# TopSheet.net
KiCad netlist of a schematic drawn in Altium Designer
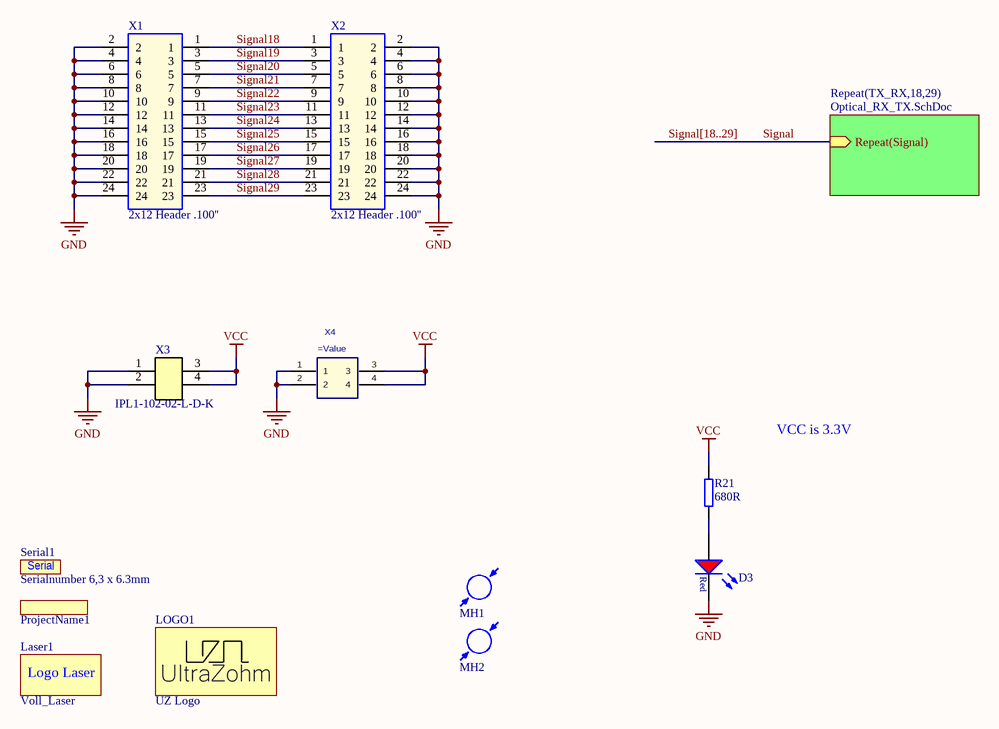
[diagram p0: TopSheet.SchDoc]

(export (version "E")
  (design (tool "Eeschema 10.0.6"))
  (components
    (comp (ref "D3")
      (value "150060RS75000")
      (footprint "WL-SMCW_0603")
      (description "WL-SMCW SMD Mono-color Chip LED Waterclear, size 0603, Red, 2 V, 140°")
      (fields
        (field (name "MF") "Wuerth Elektronik")
        (field (name "LCSC PART NUMBER") "C2286")
        (field (name "CREATED") "2018_09_06_AGeiger")
      )
      (libsource (lib "UZOhm_Optical") (part "LED_Red_0603"))
    )
    (comp (ref "Laser1")
      (value "Voll_Laser")
      (footprint "Voll_Laser")
      (description "Logo Laser Warning Sign")
      (libsource (lib "UZOhm_Optical") (part "Voll_Laser"))
    )
    (comp (ref "LOGO1")
      (value "UZ Logo")
      (footprint "UZ_Logo_small")
      (description "UltraZohm Logo on PCB")
      (fields (field (name "CREATED") "Jan2021_Liegmann"))
      (libsource (lib "PCB_Logo") (part "UZ Logo"))
    )
    (comp (ref "MH1")
      (value "MH_2.8")
      (footprint "MH_2.8")
      (description "Non plated through hole")
      (libsource (lib "UZOhm_Optical") (part "Mounting Hole"))
    )
    (comp (ref "MH2")
      (value "MH_2.8")
      (footprint "MH_2.8")
      (description "Non plated through hole")
      (libsource (lib "UZOhm_Optical") (part "Mounting Hole"))
    )
    (comp (ref "ProjectName1")
      (value "Project Name, Rev")
      (footprint "ID_ProjectRev")
      (description "Project Name and Revision Number")
      (fields (field (name "CREATED") "2018_11_23_AGeiger"))
      (libsource (lib "UZOhm_Optical") (part "ID_ProjectRev"))
    )
    (comp (ref "R21")
      (value "680R")
      (footprint "R_0603_N")
      (description "SMD Resistor 0603")
      (fields
        (field (name "TOLERANCE") "1%")
        (field (name "VOLTAGE") "75V")
        (field (name "CREATED") "2018_09_06_AGeiger")
      )
      (libsource (lib "UZOhm_Optical") (part "R_0603"))
    )
    (comp (ref "Serial1")
      (value "Serialnumber 6,3 x 6.3mm")
      (footprint "Serial_6.3x6.3mm")
      (fields (field (name "CREATED") "2018_09_18_AGeiger"))
      (libsource (lib "UZOhm_Optical") (part "SerialNumber"))
    )
    (comp (ref "X1")
      (value "2x12 Header .100''")
      (footprint "TST-112-01-G-D")
      (description "Double Row, 12 positions, Shrouded Terminal Header .100''")
      (fields
        (field (name "MF") "Samtec")
        (field (name "MPN") "TST-112-01-G-D")
        (field (name "CREATED") "2020_04_Kreppel")
      )
      (libsource (lib "") (part "TST-112-01-G-D_1"))
    )
    (comp (ref "X2")
      (value "2x12 Header .100''")
      (footprint "TST-112-01-G-D")
      (description "Double Row, 12 positions, Shrouded Terminal Header .100''")
      (fields
        (field (name "MF") "Samtec")
        (field (name "MPN") "TST-112-01-G-D")
        (field (name "CREATED") "2020_04_Kreppel")
      )
      (libsource (lib "UZOhm_Optical") (part "TST-112-01-G-D"))
    )
    (comp (ref "X3")
      (value "IPL1-102-02-L-D-K")
      (footprint "IPL1-102-02-L-D-K-0")
      (description "P=2.54mm Wire To Board Connector ROHS")
      (fields
        (field (name "MANUFACTURER") "SAMTEC")
        (field (name "LCSC PART NUMBER") "C7437440")
        (field (name "CREATED FROM") "KIlhan")
      )
      (libsource (lib "user") (part "IPL1-102-02-L-D-K"))
    )
    (comp (ref "X4")
      (value "~")
      (footprint "IPL1-102-01-L-D-K")
      (description "2.54mm Double Row Terminal Assembly, Right-Angled")
      (fields
        (field (name "MANUFACTURER") "SAMTEC")
        (field (name "LCSC PART NUMBER") "C5714565")
        (field (name "CREATED") "2018_05_02_AGeiger")
      )
      (libsource (lib "UZOhm_Optical") (part "IPL1-102-XX-X-D-X"))
    )
  )
  (nets
    (net (code "2") (name "/Signal18") (class "Default")
      (node (ref "X1") (pin "1") (pinfunction "1_1") (pintype "passive"))
      (node (ref "X2") (pin "1") (pinfunction "1_1") (pintype "passive"))
    )
    (net (code "3") (name "/Signal19") (class "Default")
      (node (ref "X1") (pin "3") (pinfunction "3_3") (pintype "passive"))
      (node (ref "X2") (pin "3") (pinfunction "3_3") (pintype "passive"))
    )
    (net (code "4") (name "/Signal20") (class "Default")
      (node (ref "X1") (pin "5") (pinfunction "5_5") (pintype "passive"))
      (node (ref "X2") (pin "5") (pinfunction "5_5") (pintype "passive"))
    )
    (net (code "5") (name "/Signal21") (class "Default")
      (node (ref "X1") (pin "7") (pinfunction "7_7") (pintype "passive"))
      (node (ref "X2") (pin "7") (pinfunction "7_7") (pintype "passive"))
    )
    (net (code "6") (name "/Signal22") (class "Default")
      (node (ref "X1") (pin "9") (pinfunction "9_9") (pintype "passive"))
      (node (ref "X2") (pin "9") (pinfunction "9_9") (pintype "passive"))
    )
    (net (code "7") (name "/Signal23") (class "Default")
      (node (ref "X1") (pin "11") (pinfunction "11_11") (pintype "passive"))
      (node (ref "X2") (pin "11") (pinfunction "11_11") (pintype "passive"))
    )
    (net (code "8") (name "/Signal24") (class "Default")
      (node (ref "X1") (pin "13") (pinfunction "13_13") (pintype "passive"))
      (node (ref "X2") (pin "13") (pinfunction "13_13") (pintype "passive"))
    )
    (net (code "9") (name "/Signal25") (class "Default")
      (node (ref "X1") (pin "15") (pinfunction "15_15") (pintype "passive"))
      (node (ref "X2") (pin "15") (pinfunction "15_15") (pintype "passive"))
    )
    (net (code "10") (name "/Signal26") (class "Default")
      (node (ref "X1") (pin "17") (pinfunction "17_17") (pintype "passive"))
      (node (ref "X2") (pin "17") (pinfunction "17_17") (pintype "passive"))
    )
    (net (code "11") (name "/Signal27") (class "Default")
      (node (ref "X1") (pin "19") (pinfunction "19_19") (pintype "passive"))
      (node (ref "X2") (pin "19") (pinfunction "19_19") (pintype "passive"))
    )
    (net (code "12") (name "/Signal28") (class "Default")
      (node (ref "X1") (pin "21") (pinfunction "21_21") (pintype "passive"))
      (node (ref "X2") (pin "21") (pinfunction "21_21") (pintype "passive"))
    )
    (net (code "13") (name "/Signal29") (class "Default")
      (node (ref "X1") (pin "23") (pinfunction "23_23") (pintype "passive"))
      (node (ref "X2") (pin "23") (pinfunction "23_23") (pintype "passive"))
    )
    (net (code "15") (name "GND") (class "Default")
      (node (ref "D3") (pin "1") (pinfunction "K_1") (pintype "passive"))
      (node (ref "X1") (pin "10") (pinfunction "10_10") (pintype "passive"))
      (node (ref "X1") (pin "12") (pinfunction "12_12") (pintype "passive"))
      (node (ref "X1") (pin "14") (pinfunction "14_14") (pintype "passive"))
      (node (ref "X1") (pin "16") (pinfunction "16_16") (pintype "passive"))
      (node (ref "X1") (pin "18") (pinfunction "18_18") (pintype "passive"))
      (node (ref "X1") (pin "2") (pinfunction "2_2") (pintype "passive"))
      (node (ref "X1") (pin "20") (pinfunction "20_20") (pintype "passive"))
      (node (ref "X1") (pin "22") (pinfunction "22_22") (pintype "passive"))
      (node (ref "X1") (pin "24") (pinfunction "24_24") (pintype "passive"))
      (node (ref "X1") (pin "4") (pinfunction "4_4") (pintype "passive"))
      (node (ref "X1") (pin "6") (pinfunction "6_6") (pintype "passive"))
      (node (ref "X1") (pin "8") (pinfunction "8_8") (pintype "passive"))
      (node (ref "X2") (pin "10") (pinfunction "10_10") (pintype "passive"))
      (node (ref "X2") (pin "12") (pinfunction "12_12") (pintype "passive"))
      (node (ref "X2") (pin "14") (pinfunction "14_14") (pintype "passive"))
      (node (ref "X2") (pin "16") (pinfunction "16_16") (pintype "passive"))
      (node (ref "X2") (pin "18") (pinfunction "18_18") (pintype "passive"))
      (node (ref "X2") (pin "2") (pinfunction "2_2") (pintype "passive"))
      (node (ref "X2") (pin "20") (pinfunction "20_20") (pintype "passive"))
      (node (ref "X2") (pin "22") (pinfunction "22_22") (pintype "passive"))
      (node (ref "X2") (pin "24") (pinfunction "24_24") (pintype "passive"))
      (node (ref "X2") (pin "4") (pinfunction "4_4") (pintype "passive"))
      (node (ref "X2") (pin "6") (pinfunction "6_6") (pintype "passive"))
      (node (ref "X2") (pin "8") (pinfunction "8_8") (pintype "passive"))
      (node (ref "X3") (pin "1") (pinfunction "1_1") (pintype "passive"))
      (node (ref "X3") (pin "2") (pinfunction "2_2") (pintype "passive"))
      (node (ref "X4") (pin "1") (pinfunction "1_1") (pintype "passive"))
      (node (ref "X4") (pin "2") (pinfunction "2_2") (pintype "passive"))
    )
    (net (code "16") (name "Net-(D3-A)") (class "Default")
      (node (ref "D3") (pin "2") (pinfunction "A_2") (pintype "passive"))
      (node (ref "R21") (pin "1") (pinfunction "1_1") (pintype "passive"))
    )
    (net (code "17") (name "VCC") (class "Default")
      (node (ref "R21") (pin "2") (pinfunction "2_2") (pintype "passive"))
      (node (ref "X3") (pin "3") (pinfunction "3_3") (pintype "passive"))
      (node (ref "X3") (pin "4") (pinfunction "4_4") (pintype "passive"))
      (node (ref "X4") (pin "3") (pinfunction "3_3") (pintype "passive"))
      (node (ref "X4") (pin "4") (pinfunction "4_4") (pintype "passive"))
    )
  )
)
